# SmartGarden_Master_v1_5.net
KiCad netlist of a schematic drawn in EAGLE
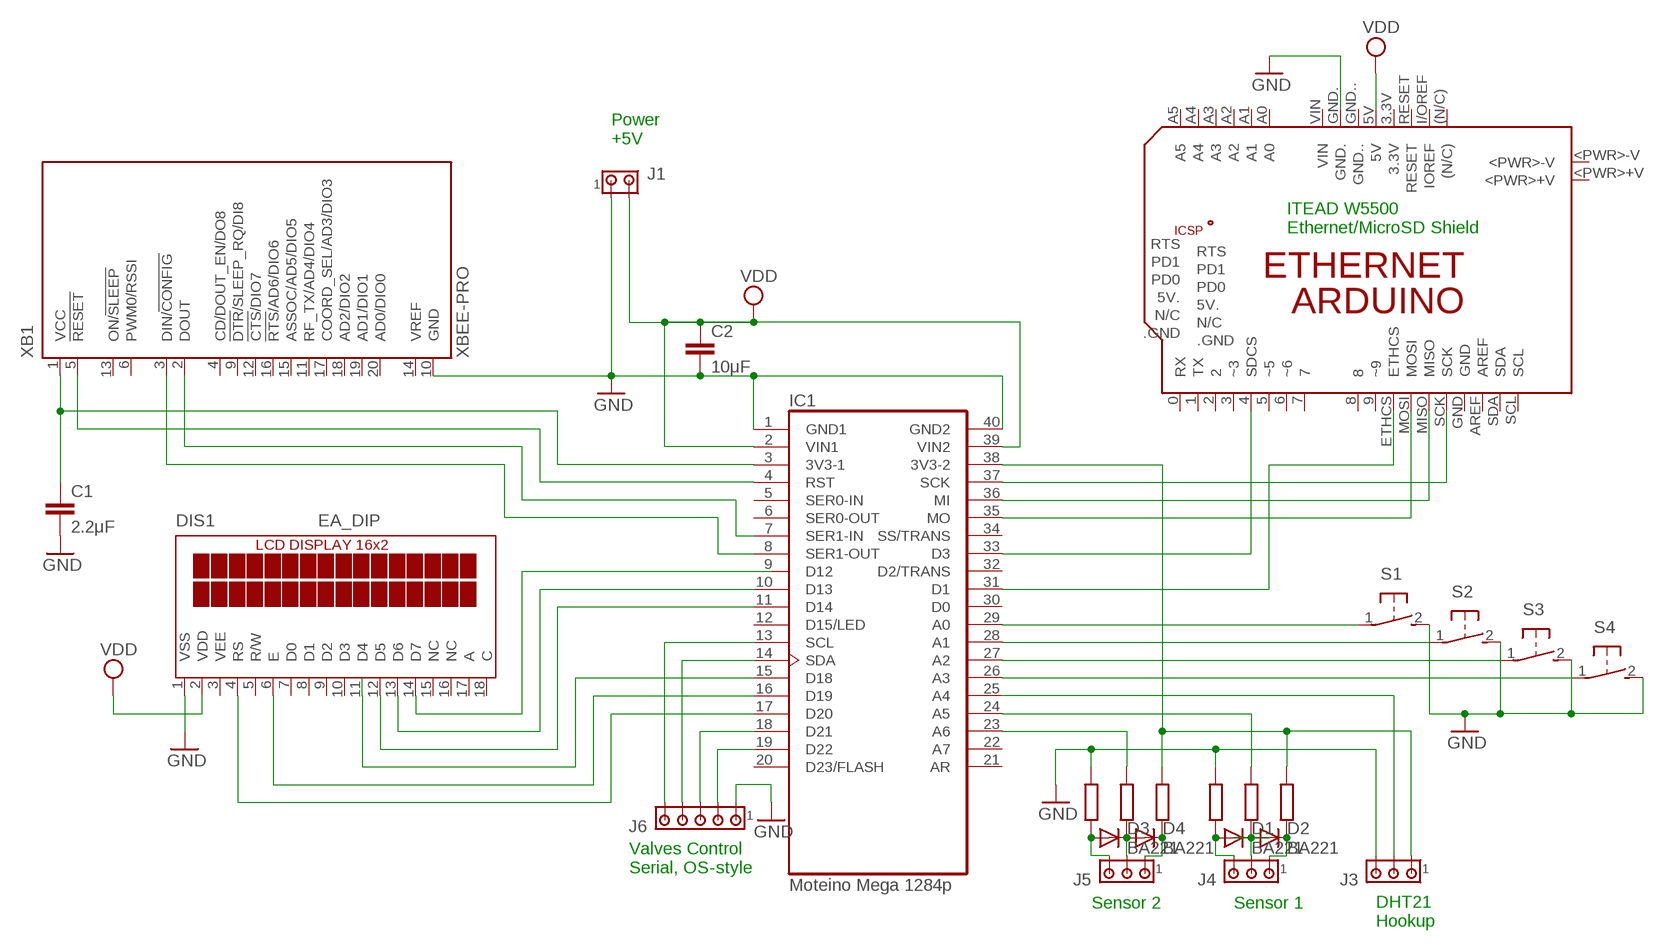
[diagram p0: schematic, sheet 1]

(export (version "E")
  (design (tool "Eeschema 10.0.6"))
  (components
    (comp (ref "C1")
      (value "2.2μF")
      (footprint "eagle-import:C050-055X075")
      (libsource (lib "eagle-import") (part "C-EU050-055X075"))
    )
    (comp (ref "C2")
      (value "10μF")
      (footprint "eagle-import:C050-035X075")
      (libsource (lib "eagle-import") (part "C-EU050-035X075"))
    )
    (comp (ref "D1")
      (value "BA221")
      (footprint "eagle-import:DO35-10")
      (libsource (lib "eagle-import") (part "BA221"))
    )
    (comp (ref "D2")
      (value "BA221")
      (footprint "eagle-import:DO35-10")
      (libsource (lib "eagle-import") (part "BA221"))
    )
    (comp (ref "D3")
      (value "BA221")
      (footprint "eagle-import:DO35-10")
      (libsource (lib "eagle-import") (part "BA221"))
    )
    (comp (ref "D4")
      (value "BA221")
      (footprint "eagle-import:DO35-10")
      (libsource (lib "eagle-import") (part "BA221"))
    )
    (comp (ref "DIS1")
      (value "EA_DIP")
      (footprint "eagle-import:EA_DIP")
      (libsource (lib "eagle-import") (part "EA_DIP"))
    )
    (comp (ref "IC1")
      (value "Moteino Mega 1284p")
      (footprint "eagle-import:DIL40")
      (libsource (lib "eagle-import") (part "MOTEINO_MEGA"))
    )
    (comp (ref "J1")
      (value "MTA02-156")
      (footprint "eagle-import:1X2MTA")
      (libsource (lib "eagle-import") (part "MTA02-156"))
    )
    (comp (ref "J3")
      (value "MTA03-156")
      (footprint "eagle-import:1X3MTA")
      (libsource (lib "eagle-import") (part "MTA03-156"))
    )
    (comp (ref "J4")
      (value "MTA03-156")
      (footprint "eagle-import:1X3MTA")
      (libsource (lib "eagle-import") (part "MTA03-156"))
    )
    (comp (ref "J5")
      (value "MTA03-156")
      (footprint "eagle-import:1X3MTA")
      (libsource (lib "eagle-import") (part "MTA03-156"))
    )
    (comp (ref "J6")
      (value "MTA05-100")
      (footprint "eagle-import:10X05MTA")
      (libsource (lib "eagle-import") (part "MTA05-100"))
    )
    (comp (ref "PCB1")
      (value "ARDUINO_ETHERNET")
      (footprint "eagle-import:ARDUINO_ETHERNET")
      (libsource (lib "eagle-import") (part "ARDUINO_ETHERNET"))
    )
    (comp (ref "S1")
      (value "31-XX")
      (footprint "eagle-import:B3F-31XX")
      (fields (field (name "MPN") "B3F-3100"))
      (libsource (lib "eagle-import") (part "31-XX"))
    )
    (comp (ref "S2")
      (value "31-XX")
      (footprint "eagle-import:B3F-31XX")
      (fields (field (name "MPN") "B3F-3100"))
      (libsource (lib "eagle-import") (part "31-XX"))
    )
    (comp (ref "S3")
      (value "31-XX")
      (footprint "eagle-import:B3F-31XX")
      (fields (field (name "MPN") "B3F-3100"))
      (libsource (lib "eagle-import") (part "31-XX"))
    )
    (comp (ref "S4")
      (value "31-XX")
      (footprint "eagle-import:B3F-31XX")
      (fields (field (name "MPN") "B3F-3100"))
      (libsource (lib "eagle-import") (part "31-XX"))
    )
    (comp (ref "XB1")
      (value "XBEE-PRO")
      (footprint "eagle-import:XBEE-PRO")
      (fields (field (name "MPN") "XBP24-AWI-001"))
      (libsource (lib "eagle-import") (part "XBEE-PRO"))
    )
  )
  (nets
    (net (code "1") (name "/VEE") (class "Default")
      (node (ref "DIS1") (pin "3") (pinfunction "VEE_3") (pintype "power_in"))
    )
    (net (code "2") (name "GND") (class "Default")
      (node (ref "C1") (pin "2") (pinfunction "2_2") (pintype "passive"))
      (node (ref "C2") (pin "2") (pinfunction "2_2") (pintype "passive"))
      (node (ref "DIS1") (pin "1") (pinfunction "VSS_1") (pintype "power_in"))
      (node (ref "IC1") (pin "1") (pinfunction "GND1_1") (pintype "power_in"))
      (node (ref "IC1") (pin "40") (pinfunction "GND2_40") (pintype "power_in"))
      (node (ref "J1") (pin "1") (pinfunction "1_1") (pintype "passive"))
      (node (ref "J3") (pin "3") (pinfunction "3_3") (pintype "passive"))
      (node (ref "J6") (pin "1") (pinfunction "1_1") (pintype "passive"))
      (node (ref "PCB1") (pin "GND.") (pinfunction "GND._GND.") (pintype "bidirectional"))
      (node (ref "S1") (pin "2") (pinfunction "S_2") (pintype "passive"))
      (node (ref "S2") (pin "2") (pinfunction "S_2") (pintype "passive"))
      (node (ref "S3") (pin "2") (pinfunction "S_2") (pintype "passive"))
      (node (ref "S4") (pin "2") (pinfunction "S_2") (pintype "passive"))
      (node (ref "XB1") (pin "10") (pinfunction "GND_10") (pintype "power_in"))
    )
    (net (code "3") (name "Net-(D1-PadA)") (class "Default")
      (node (ref "D1") (pin "A") (pinfunction "A_A") (pintype "passive"))
      (node (ref "J4") (pin "3") (pinfunction "3_3") (pintype "passive"))
    )
    (net (code "4") (name "Net-(D1-PadC)") (class "Default")
      (node (ref "D1") (pin "C") (pinfunction "C_C") (pintype "passive"))
      (node (ref "D2") (pin "A") (pinfunction "A_A") (pintype "passive"))
      (node (ref "J4") (pin "2") (pinfunction "2_2") (pintype "passive"))
    )
    (net (code "5") (name "Net-(D2-PadC)") (class "Default")
      (node (ref "D2") (pin "C") (pinfunction "C_C") (pintype "passive"))
      (node (ref "J4") (pin "1") (pinfunction "1_1") (pintype "passive"))
    )
    (net (code "6") (name "Net-(D3-PadA)") (class "Default")
      (node (ref "D3") (pin "A") (pinfunction "A_A") (pintype "passive"))
      (node (ref "J5") (pin "3") (pinfunction "3_3") (pintype "passive"))
    )
    (net (code "7") (name "Net-(D3-PadC)") (class "Default")
      (node (ref "D3") (pin "C") (pinfunction "C_C") (pintype "passive"))
      (node (ref "D4") (pin "A") (pinfunction "A_A") (pintype "passive"))
      (node (ref "J5") (pin "2") (pinfunction "2_2") (pintype "passive"))
    )
    (net (code "8") (name "Net-(D4-PadC)") (class "Default")
      (node (ref "D4") (pin "C") (pinfunction "C_C") (pintype "passive"))
      (node (ref "J5") (pin "1") (pinfunction "1_1") (pintype "passive"))
    )
    (net (code "9") (name "Net-(DIS1-D4)") (class "Default")
      (node (ref "DIS1") (pin "11") (pinfunction "D4_11") (pintype "input"))
      (node (ref "IC1") (pin "15") (pinfunction "D18_15") (pintype "bidirectional"))
    )
    (net (code "10") (name "Net-(DIS1-D5)") (class "Default")
      (node (ref "DIS1") (pin "12") (pinfunction "D5_12") (pintype "input"))
      (node (ref "IC1") (pin "11") (pinfunction "D14_11") (pintype "bidirectional"))
    )
    (net (code "11") (name "Net-(DIS1-D6)") (class "Default")
      (node (ref "DIS1") (pin "13") (pinfunction "D6_13") (pintype "input"))
      (node (ref "IC1") (pin "10") (pinfunction "D13_10") (pintype "bidirectional"))
    )
    (net (code "12") (name "Net-(DIS1-E)") (class "Default")
      (node (ref "DIS1") (pin "6") (pinfunction "E_6") (pintype "input"))
      (node (ref "IC1") (pin "16") (pinfunction "D19_16") (pintype "bidirectional"))
    )
    (net (code "13") (name "Net-(DIS1-RS)") (class "Default")
      (node (ref "DIS1") (pin "4") (pinfunction "RS_4") (pintype "input"))
      (node (ref "IC1") (pin "17") (pinfunction "D20_17") (pintype "bidirectional"))
    )
    (net (code "14") (name "Net-(IC1-3V3-1)") (class "Default")
      (node (ref "C1") (pin "1") (pinfunction "1_1") (pintype "passive"))
      (node (ref "IC1") (pin "3") (pinfunction "3V3-1_3") (pintype "output"))
      (node (ref "XB1") (pin "1") (pinfunction "VCC_1") (pintype "power_in"))
    )
    (net (code "15") (name "Net-(IC1-3V3-2)") (class "Default")
      (node (ref "IC1") (pin "38") (pinfunction "3V3-2_38") (pintype "output"))
      (node (ref "J3") (pin "1") (pinfunction "1_1") (pintype "passive"))
    )
    (net (code "16") (name "Net-(IC1-A0)") (class "Default")
      (node (ref "IC1") (pin "29") (pinfunction "A0_29") (pintype "bidirectional"))
      (node (ref "S1") (pin "1") (pinfunction "P_1") (pintype "passive"))
    )
    (net (code "17") (name "Net-(IC1-A1)") (class "Default")
      (node (ref "IC1") (pin "28") (pinfunction "A1_28") (pintype "bidirectional"))
      (node (ref "S2") (pin "1") (pinfunction "P_1") (pintype "passive"))
    )
    (net (code "18") (name "Net-(IC1-A2)") (class "Default")
      (node (ref "IC1") (pin "27") (pinfunction "A2_27") (pintype "bidirectional"))
      (node (ref "S3") (pin "1") (pinfunction "P_1") (pintype "passive"))
    )
    (net (code "19") (name "Net-(IC1-A3)") (class "Default")
      (node (ref "IC1") (pin "26") (pinfunction "A3_26") (pintype "bidirectional"))
      (node (ref "S4") (pin "1") (pinfunction "P_1") (pintype "passive"))
    )
    (net (code "20") (name "Net-(IC1-A4)") (class "Default")
      (node (ref "IC1") (pin "25") (pinfunction "A4_25") (pintype "bidirectional"))
      (node (ref "J3") (pin "2") (pinfunction "2_2") (pintype "passive"))
    )
    (net (code "21") (name "Net-(IC1-D1)") (class "Default")
      (node (ref "IC1") (pin "31") (pinfunction "D1_31") (pintype "bidirectional"))
      (node (ref "PCB1") (pin "ETHCS") (pinfunction "ETHCS_ETHCS") (pintype "bidirectional"))
    )
    (net (code "22") (name "Net-(IC1-D3)") (class "Default")
      (node (ref "IC1") (pin "33") (pinfunction "D3_33") (pintype "bidirectional"))
      (node (ref "PCB1") (pin "4") (pinfunction "SDCS_4") (pintype "bidirectional"))
    )
    (net (code "23") (name "Net-(IC1-D21)") (class "Default")
      (node (ref "IC1") (pin "18") (pinfunction "D21_18") (pintype "bidirectional"))
      (node (ref "J6") (pin "3") (pinfunction "3_3") (pintype "passive"))
    )
    (net (code "24") (name "Net-(IC1-D22)") (class "Default")
      (node (ref "IC1") (pin "19") (pinfunction "D22_19") (pintype "bidirectional"))
      (node (ref "J6") (pin "2") (pinfunction "2_2") (pintype "passive"))
    )
    (net (code "25") (name "Net-(IC1-MI)") (class "Default")
      (node (ref "IC1") (pin "36") (pinfunction "MI_36") (pintype "bidirectional"))
      (node (ref "PCB1") (pin "MISO") (pinfunction "MISO_MISO") (pintype "bidirectional"))
    )
    (net (code "26") (name "Net-(IC1-MO)") (class "Default")
      (node (ref "IC1") (pin "35") (pinfunction "MO_35") (pintype "bidirectional"))
      (node (ref "PCB1") (pin "MOSI") (pinfunction "MOSI_MOSI") (pintype "bidirectional"))
    )
    (net (code "27") (name "Net-(IC1-RST)") (class "Default")
      (node (ref "IC1") (pin "4") (pinfunction "RST_4") (pintype "bidirectional"))
      (node (ref "XB1") (pin "5") (pinfunction "~{RESET}_5") (pintype "input"))
    )
    (net (code "28") (name "Net-(IC1-SCK)") (class "Default")
      (node (ref "IC1") (pin "37") (pinfunction "SCK_37") (pintype "bidirectional"))
      (node (ref "PCB1") (pin "SCK") (pinfunction "SCK_SCK") (pintype "bidirectional"))
    )
    (net (code "29") (name "Net-(IC1-SCL)") (class "Default")
      (node (ref "IC1") (pin "13") (pinfunction "SCL_13") (pintype "bidirectional"))
      (node (ref "J6") (pin "5") (pinfunction "5_5") (pintype "passive"))
    )
    (net (code "30") (name "Net-(IC1-SDA)") (class "Default")
      (node (ref "IC1") (pin "14") (pinfunction "SDA_14") (pintype "input"))
      (node (ref "J6") (pin "4") (pinfunction "4_4") (pintype "passive"))
    )
    (net (code "31") (name "Net-(IC1-SER1-IN)") (class "Default")
      (node (ref "IC1") (pin "7") (pinfunction "SER1-IN_7") (pintype "bidirectional"))
      (node (ref "XB1") (pin "2") (pinfunction "DOUT_2") (pintype "output"))
    )
    (net (code "32") (name "Net-(IC1-SER1-OUT)") (class "Default")
      (node (ref "IC1") (pin "8") (pinfunction "SER1-OUT_8") (pintype "bidirectional"))
      (node (ref "XB1") (pin "3") (pinfunction "DIN/~{CONFIG}_3") (pintype "input"))
    )
    (net (code "33") (name "VDD") (class "Default")
      (node (ref "C2") (pin "1") (pinfunction "1_1") (pintype "passive"))
      (node (ref "DIS1") (pin "2") (pinfunction "VDD_2") (pintype "power_in"))
      (node (ref "IC1") (pin "2") (pinfunction "VIN1_2") (pintype "power_in"))
      (node (ref "IC1") (pin "39") (pinfunction "VIN2_39") (pintype "power_in"))
      (node (ref "J1") (pin "2") (pinfunction "2_2") (pintype "passive"))
      (node (ref "PCB1") (pin "5V") (pinfunction "5V_5V") (pintype "bidirectional"))
    )
    (net (code "34") (name "unconnected-(DIS1-A-Pad17)") (class "Default")
      (node (ref "DIS1") (pin "17") (pinfunction "A_17") (pintype "passive"))
    )
    (net (code "35") (name "unconnected-(DIS1-C-Pad18)") (class "Default")
      (node (ref "DIS1") (pin "18") (pinfunction "C_18") (pintype "passive"))
    )
    (net (code "36") (name "unconnected-(DIS1-D0-Pad7)") (class "Default")
      (node (ref "DIS1") (pin "7") (pinfunction "D0_7") (pintype "input"))
    )
    (net (code "37") (name "unconnected-(DIS1-D1-Pad8)") (class "Default")
      (node (ref "DIS1") (pin "8") (pinfunction "D1_8") (pintype "input"))
    )
    (net (code "38") (name "unconnected-(DIS1-D2-Pad9)") (class "Default")
      (node (ref "DIS1") (pin "9") (pinfunction "D2_9") (pintype "input"))
    )
    (net (code "39") (name "unconnected-(DIS1-D3-Pad10)") (class "Default")
      (node (ref "DIS1") (pin "10") (pinfunction "D3_10") (pintype "input"))
    )
    (net (code "40") (name "unconnected-(DIS1-D7-Pad14)") (class "Default")
      (node (ref "DIS1") (pin "14") (pinfunction "D7_14") (pintype "input"))
    )
    (net (code "41") (name "unconnected-(DIS1-NC-Pad15)") (class "Default")
      (node (ref "DIS1") (pin "15") (pinfunction "NC_15") (pintype "no_connect"))
    )
    (net (code "42") (name "unconnected-(DIS1-NC-Pad16)") (class "Default")
      (node (ref "DIS1") (pin "16") (pinfunction "NC_16") (pintype "no_connect"))
    )
    (net (code "43") (name "unconnected-(DIS1-R{slash}W-Pad5)") (class "Default")
      (node (ref "DIS1") (pin "5") (pinfunction "R/W_5") (pintype "input"))
    )
    (net (code "44") (name "unconnected-(IC1-A5-Pad24)") (class "Default")
      (node (ref "IC1") (pin "24") (pinfunction "A5_24") (pintype "bidirectional"))
    )
    (net (code "45") (name "unconnected-(IC1-A6-Pad23)") (class "Default")
      (node (ref "IC1") (pin "23") (pinfunction "A6_23") (pintype "bidirectional"))
    )
    (net (code "46") (name "unconnected-(IC1-A7-Pad22)") (class "Default")
      (node (ref "IC1") (pin "22") (pinfunction "A7_22") (pintype "bidirectional"))
    )
    (net (code "47") (name "unconnected-(IC1-AR-Pad21)") (class "Default")
      (node (ref "IC1") (pin "21") (pinfunction "AR_21") (pintype "bidirectional"))
    )
    (net (code "48") (name "unconnected-(IC1-D0-Pad30)") (class "Default")
      (node (ref "IC1") (pin "30") (pinfunction "D0_30") (pintype "bidirectional"))
    )
    (net (code "49") (name "unconnected-(IC1-D2{slash}TRANS-Pad32)") (class "Default")
      (node (ref "IC1") (pin "32") (pinfunction "D2/TRANS_32") (pintype "bidirectional"))
    )
    (net (code "50") (name "unconnected-(IC1-D12-Pad9)") (class "Default")
      (node (ref "IC1") (pin "9") (pinfunction "D12_9") (pintype "bidirectional"))
    )
    (net (code "51") (name "unconnected-(IC1-D15{slash}LED-Pad12)") (class "Default")
      (node (ref "IC1") (pin "12") (pinfunction "D15/LED_12") (pintype "bidirectional"))
    )
    (net (code "52") (name "unconnected-(IC1-D23{slash}FLASH-Pad20)") (class "Default")
      (node (ref "IC1") (pin "20") (pinfunction "D23/FLASH_20") (pintype "bidirectional"))
    )
    (net (code "53") (name "unconnected-(IC1-SER0-IN-Pad5)") (class "Default")
      (node (ref "IC1") (pin "5") (pinfunction "SER0-IN_5") (pintype "bidirectional"))
    )
    (net (code "54") (name "unconnected-(IC1-SER0-OUT-Pad6)") (class "Default")
      (node (ref "IC1") (pin "6") (pinfunction "SER0-OUT_6") (pintype "bidirectional"))
    )
    (net (code "55") (name "unconnected-(IC1-SS{slash}TRANS-Pad34)") (class "Default")
      (node (ref "IC1") (pin "34") (pinfunction "SS/TRANS_34") (pintype "bidirectional"))
    )
    (net (code "56") (name "unconnected-(PCB1-IOREF-PadI{slash}OREF)") (class "Default")
      (node (ref "PCB1") (pin "I/OREF") (pinfunction "IOREF_I/OREF") (pintype "bidirectional"))
    )
    (net (code "57") (name "unconnected-(PCB1-Pad(N{slash}C))") (class "Default")
      (node (ref "PCB1") (pin "(N/C)") (pinfunction "(N/C)_(N/C)") (pintype "bidirectional"))
    )
    (net (code "58") (name "unconnected-(PCB1-Pad+5V.)") (class "Default")
      (node (ref "PCB1") (pin "+5V.") (pinfunction "+5V._+5V.") (pintype "bidirectional"))
    )
    (net (code "59") (name "unconnected-(PCB1-Pad.GND)") (class "Default")
      (node (ref "PCB1") (pin ".GND") (pinfunction ".GND_.GND") (pintype "bidirectional"))
    )
    (net (code "60") (name "unconnected-(PCB1-Pad2)") (class "Default")
      (node (ref "PCB1") (pin "2") (pinfunction "2_2") (pintype "bidirectional"))
    )
    (net (code "61") (name "unconnected-(PCB1-Pad3.3V)") (class "Default")
      (node (ref "PCB1") (pin "3.3V") (pinfunction "3.3V_3.3V") (pintype "bidirectional"))
    )
    (net (code "62") (name "unconnected-(PCB1-Pad5V.)") (class "Default")
      (node (ref "PCB1") (pin "5V.") (pinfunction "5V._5V.") (pintype "bidirectional"))
    )
    (net (code "63") (name "unconnected-(PCB1-Pad7)") (class "Default")
      (node (ref "PCB1") (pin "7") (pinfunction "7_7") (pintype "bidirectional"))
    )
    (net (code "64") (name "unconnected-(PCB1-Pad8)") (class "Default")
      (node (ref "PCB1") (pin "8") (pinfunction "8_8") (pintype "bidirectional"))
    )
    (net (code "65") (name "unconnected-(PCB1-Pad<PWR>+V)") (class "Default")
      (node (ref "PCB1") (pin "<PWR>+V") (pinfunction "<PWR>+V_<PWR>+V") (pintype "bidirectional"))
    )
    (net (code "66") (name "unconnected-(PCB1-Pad<PWR>-V)") (class "Default")
      (node (ref "PCB1") (pin "<PWR>-V") (pinfunction "<PWR>-V_<PWR>-V") (pintype "bidirectional"))
    )
    (net (code "67") (name "unconnected-(PCB1-PadA0)") (class "Default")
      (node (ref "PCB1") (pin "A0") (pinfunction "A0_A0") (pintype "bidirectional"))
    )
    (net (code "68") (name "unconnected-(PCB1-PadA1)") (class "Default")
      (node (ref "PCB1") (pin "A1") (pinfunction "A1_A1") (pintype "bidirectional"))
    )
    (net (code "69") (name "unconnected-(PCB1-PadA2)") (class "Default")
      (node (ref "PCB1") (pin "A2") (pinfunction "A2_A2") (pintype "bidirectional"))
    )
    (net (code "70") (name "unconnected-(PCB1-PadA3)") (class "Default")
      (node (ref "PCB1") (pin "A3") (pinfunction "A3_A3") (pintype "bidirectional"))
    )
    (net (code "71") (name "unconnected-(PCB1-PadA4)") (class "Default")
      (node (ref "PCB1") (pin "A4") (pinfunction "A4_A4") (pintype "bidirectional"))
    )
    (net (code "72") (name "unconnected-(PCB1-PadA5)") (class "Default")
      (node (ref "PCB1") (pin "A5") (pinfunction "A5_A5") (pintype "bidirectional"))
    )
    (net (code "73") (name "unconnected-(PCB1-PadAREF)") (class "Default")
      (node (ref "PCB1") (pin "AREF") (pinfunction "AREF_AREF") (pintype "bidirectional"))
    )
    (net (code "74") (name "unconnected-(PCB1-PadGND)") (class "Default")
      (node (ref "PCB1") (pin "GND") (pinfunction "GND_GND") (pintype "bidirectional"))
    )
    (net (code "75") (name "unconnected-(PCB1-PadGND..)") (class "Default")
      (node (ref "PCB1") (pin "GND..") (pinfunction "GND.._GND..") (pintype "bidirectional"))
    )
    (net (code "76") (name "unconnected-(PCB1-PadGND_)") (class "Default")
      (node (ref "PCB1") (pin "GND_") (pinfunction "GND__GND_") (pintype "bidirectional"))
    )
    (net (code "77") (name "unconnected-(PCB1-PadMISO.)") (class "Default")
      (node (ref "PCB1") (pin "MISO.") (pinfunction "MISO._MISO.") (pintype "bidirectional"))
    )
    (net (code "78") (name "unconnected-(PCB1-PadMOSI.)") (class "Default")
      (node (ref "PCB1") (pin "MOSI.") (pinfunction "MOSI._MOSI.") (pintype "bidirectional"))
    )
    (net (code "79") (name "unconnected-(PCB1-PadN{slash}C)") (class "Default")
      (node (ref "PCB1") (pin "N/C") (pinfunction "N/C_N/C") (pintype "bidirectional"))
    )
    (net (code "80") (name "unconnected-(PCB1-PadPD0)") (class "Default")
      (node (ref "PCB1") (pin "PD0") (pinfunction "PD0_PD0") (pintype "bidirectional"))
    )
    (net (code "81") (name "unconnected-(PCB1-PadPD1)") (class "Default")
      (node (ref "PCB1") (pin "PD1") (pinfunction "PD1_PD1") (pintype "bidirectional"))
    )
    (net (code "82") (name "unconnected-(PCB1-PadRESET)") (class "Default")
      (node (ref "PCB1") (pin "RESET") (pinfunction "RESET_RESET") (pintype "bidirectional"))
    )
    (net (code "83") (name "unconnected-(PCB1-PadRESET.)") (class "Default")
      (node (ref "PCB1") (pin "RESET.") (pinfunction "RESET._RESET.") (pintype "bidirectional"))
    )
    (net (code "84") (name "unconnected-(PCB1-PadRTS)") (class "Default")
      (node (ref "PCB1") (pin "RTS") (pinfunction "RTS_RTS") (pintype "bidirectional"))
    )
    (net (code "85") (name "unconnected-(PCB1-PadSCK.)") (class "Default")
      (node (ref "PCB1") (pin "SCK.") (pinfunction "SCK._SCK.") (pintype "bidirectional"))
    )
    (net (code "86") (name "unconnected-(PCB1-PadSCL)") (class "Default")
      (node (ref "PCB1") (pin "SCL") (pinfunction "SCL_SCL") (pintype "bidirectional"))
    )
    (net (code "87") (name "unconnected-(PCB1-PadSDA)") (class "Default")
      (node (ref "PCB1") (pin "SDA") (pinfunction "SDA_SDA") (pintype "bidirectional"))
    )
    (net (code "88") (name "unconnected-(PCB1-PadVIN)") (class "Default")
      (node (ref "PCB1") (pin "VIN") (pinfunction "VIN_VIN") (pintype "bidirectional"))
    )
    (net (code "89") (name "unconnected-(PCB1-RX-Pad0)") (class "Default")
      (node (ref "PCB1") (pin "0") (pinfunction "RX_0") (pintype "bidirectional"))
    )
    (net (code "90") (name "unconnected-(PCB1-TX-Pad1)") (class "Default")
      (node (ref "PCB1") (pin "1") (pinfunction "TX_1") (pintype "bidirectional"))
    )
    (net (code "91") (name "unconnected-(PCB1-~{3}-Pad3)") (class "Default")
      (node (ref "PCB1") (pin "3") (pinfunction "~{3}_3") (pintype "bidirectional"))
    )
    (net (code "92") (name "unconnected-(PCB1-~{5}-Pad5)") (class "Default")
      (node (ref "PCB1") (pin "5") (pinfunction "~{5}_5") (pintype "bidirectional"))
    )
    (net (code "93") (name "unconnected-(PCB1-~{6}-Pad6)") (class "Default")
      (node (ref "PCB1") (pin "6") (pinfunction "~{6}_6") (pintype "bidirectional"))
    )
    (net (code "94") (name "unconnected-(PCB1-~{9}-Pad9)") (class "Default")
      (node (ref "PCB1") (pin "9") (pinfunction "~{9}_9") (pintype "bidirectional"))
    )
    (net (code "95") (name "unconnected-(XB1-AD0{slash}DIO0-Pad20)") (class "Default")
      (node (ref "XB1") (pin "20") (pinfunction "AD0/DIO0_20") (pintype "bidirectional"))
    )
    (net (code "96") (name "unconnected-(XB1-AD1{slash}DIO1-Pad19)") (class "Default")
      (node (ref "XB1") (pin "19") (pinfunction "AD1/DIO1_19") (pintype "bidirectional"))
    )
    (net (code "97") (name "unconnected-(XB1-AD2{slash}DIO2-Pad18)") (class "Default")
      (node (ref "XB1") (pin "18") (pinfunction "AD2/DIO2_18") (pintype "bidirectional"))
    )
    (net (code "98") (name "unconnected-(XB1-ASSOC{slash}AD5{slash}DIO5-Pad15)") (class "Default")
      (node (ref "XB1") (pin "15") (pinfunction "ASSOC/AD5/DIO5_15") (pintype "bidirectional"))
    )
    (net (code "99") (name "unconnected-(XB1-CD{slash}DOUT_EN{slash}DO8-Pad4)") (class "Default")
      (node (ref "XB1") (pin "4") (pinfunction "CD/DOUT_EN/DO8_4") (pintype "output"))
    )
    (net (code "100") (name "unconnected-(XB1-COORD_SEL{slash}AD3{slash}DIO3-Pad17)") (class "Default")
      (node (ref "XB1") (pin "17") (pinfunction "COORD_SEL/AD3/DIO3_17") (pintype "bidirectional"))
    )
    (net (code "101") (name "unconnected-(XB1-ON{slash}~{SLEEP}-Pad13)") (class "Default")
      (node (ref "XB1") (pin "13") (pinfunction "ON/~{SLEEP}_13") (pintype "output"))
    )
    (net (code "102") (name "unconnected-(XB1-PWM0{slash}RSSI-Pad6)") (class "Default")
      (node (ref "XB1") (pin "6") (pinfunction "PWM0/RSSI_6") (pintype "output"))
    )
    (net (code "103") (name "unconnected-(XB1-RF_TX{slash}AD4{slash}DIO4-Pad11)") (class "Default")
      (node (ref "XB1") (pin "11") (pinfunction "RF_TX/AD4/DIO4_11") (pintype "bidirectional"))
    )
    (net (code "104") (name "unconnected-(XB1-VREF-Pad14)") (class "Default")
      (node (ref "XB1") (pin "14") (pinfunction "VREF_14") (pintype "input"))
    )
    (net (code "105") (name "unconnected-(XB1-~{CTS}{slash}DIO7-Pad12)") (class "Default")
      (node (ref "XB1") (pin "12") (pinfunction "~{CTS}/DIO7_12") (pintype "bidirectional"))
    )
    (net (code "106") (name "unconnected-(XB1-~{DTR}{slash}SLEEP_RQ{slash}DI8-Pad9)") (class "Default")
      (node (ref "XB1") (pin "9") (pinfunction "~{DTR}/SLEEP_RQ/DI8_9") (pintype "bidirectional"))
    )
    (net (code "107") (name "unconnected-(XB1-~{RTS}{slash}AD6{slash}DIO6-Pad16)") (class "Default")
      (node (ref "XB1") (pin "16") (pinfunction "~{RTS}/AD6/DIO6_16") (pintype "bidirectional"))
    )
  )
)
